# ProProject_f401_audio_adc_2024-01-29.net
KiCad netlist of a schematic drawn in EasyEDA Pro
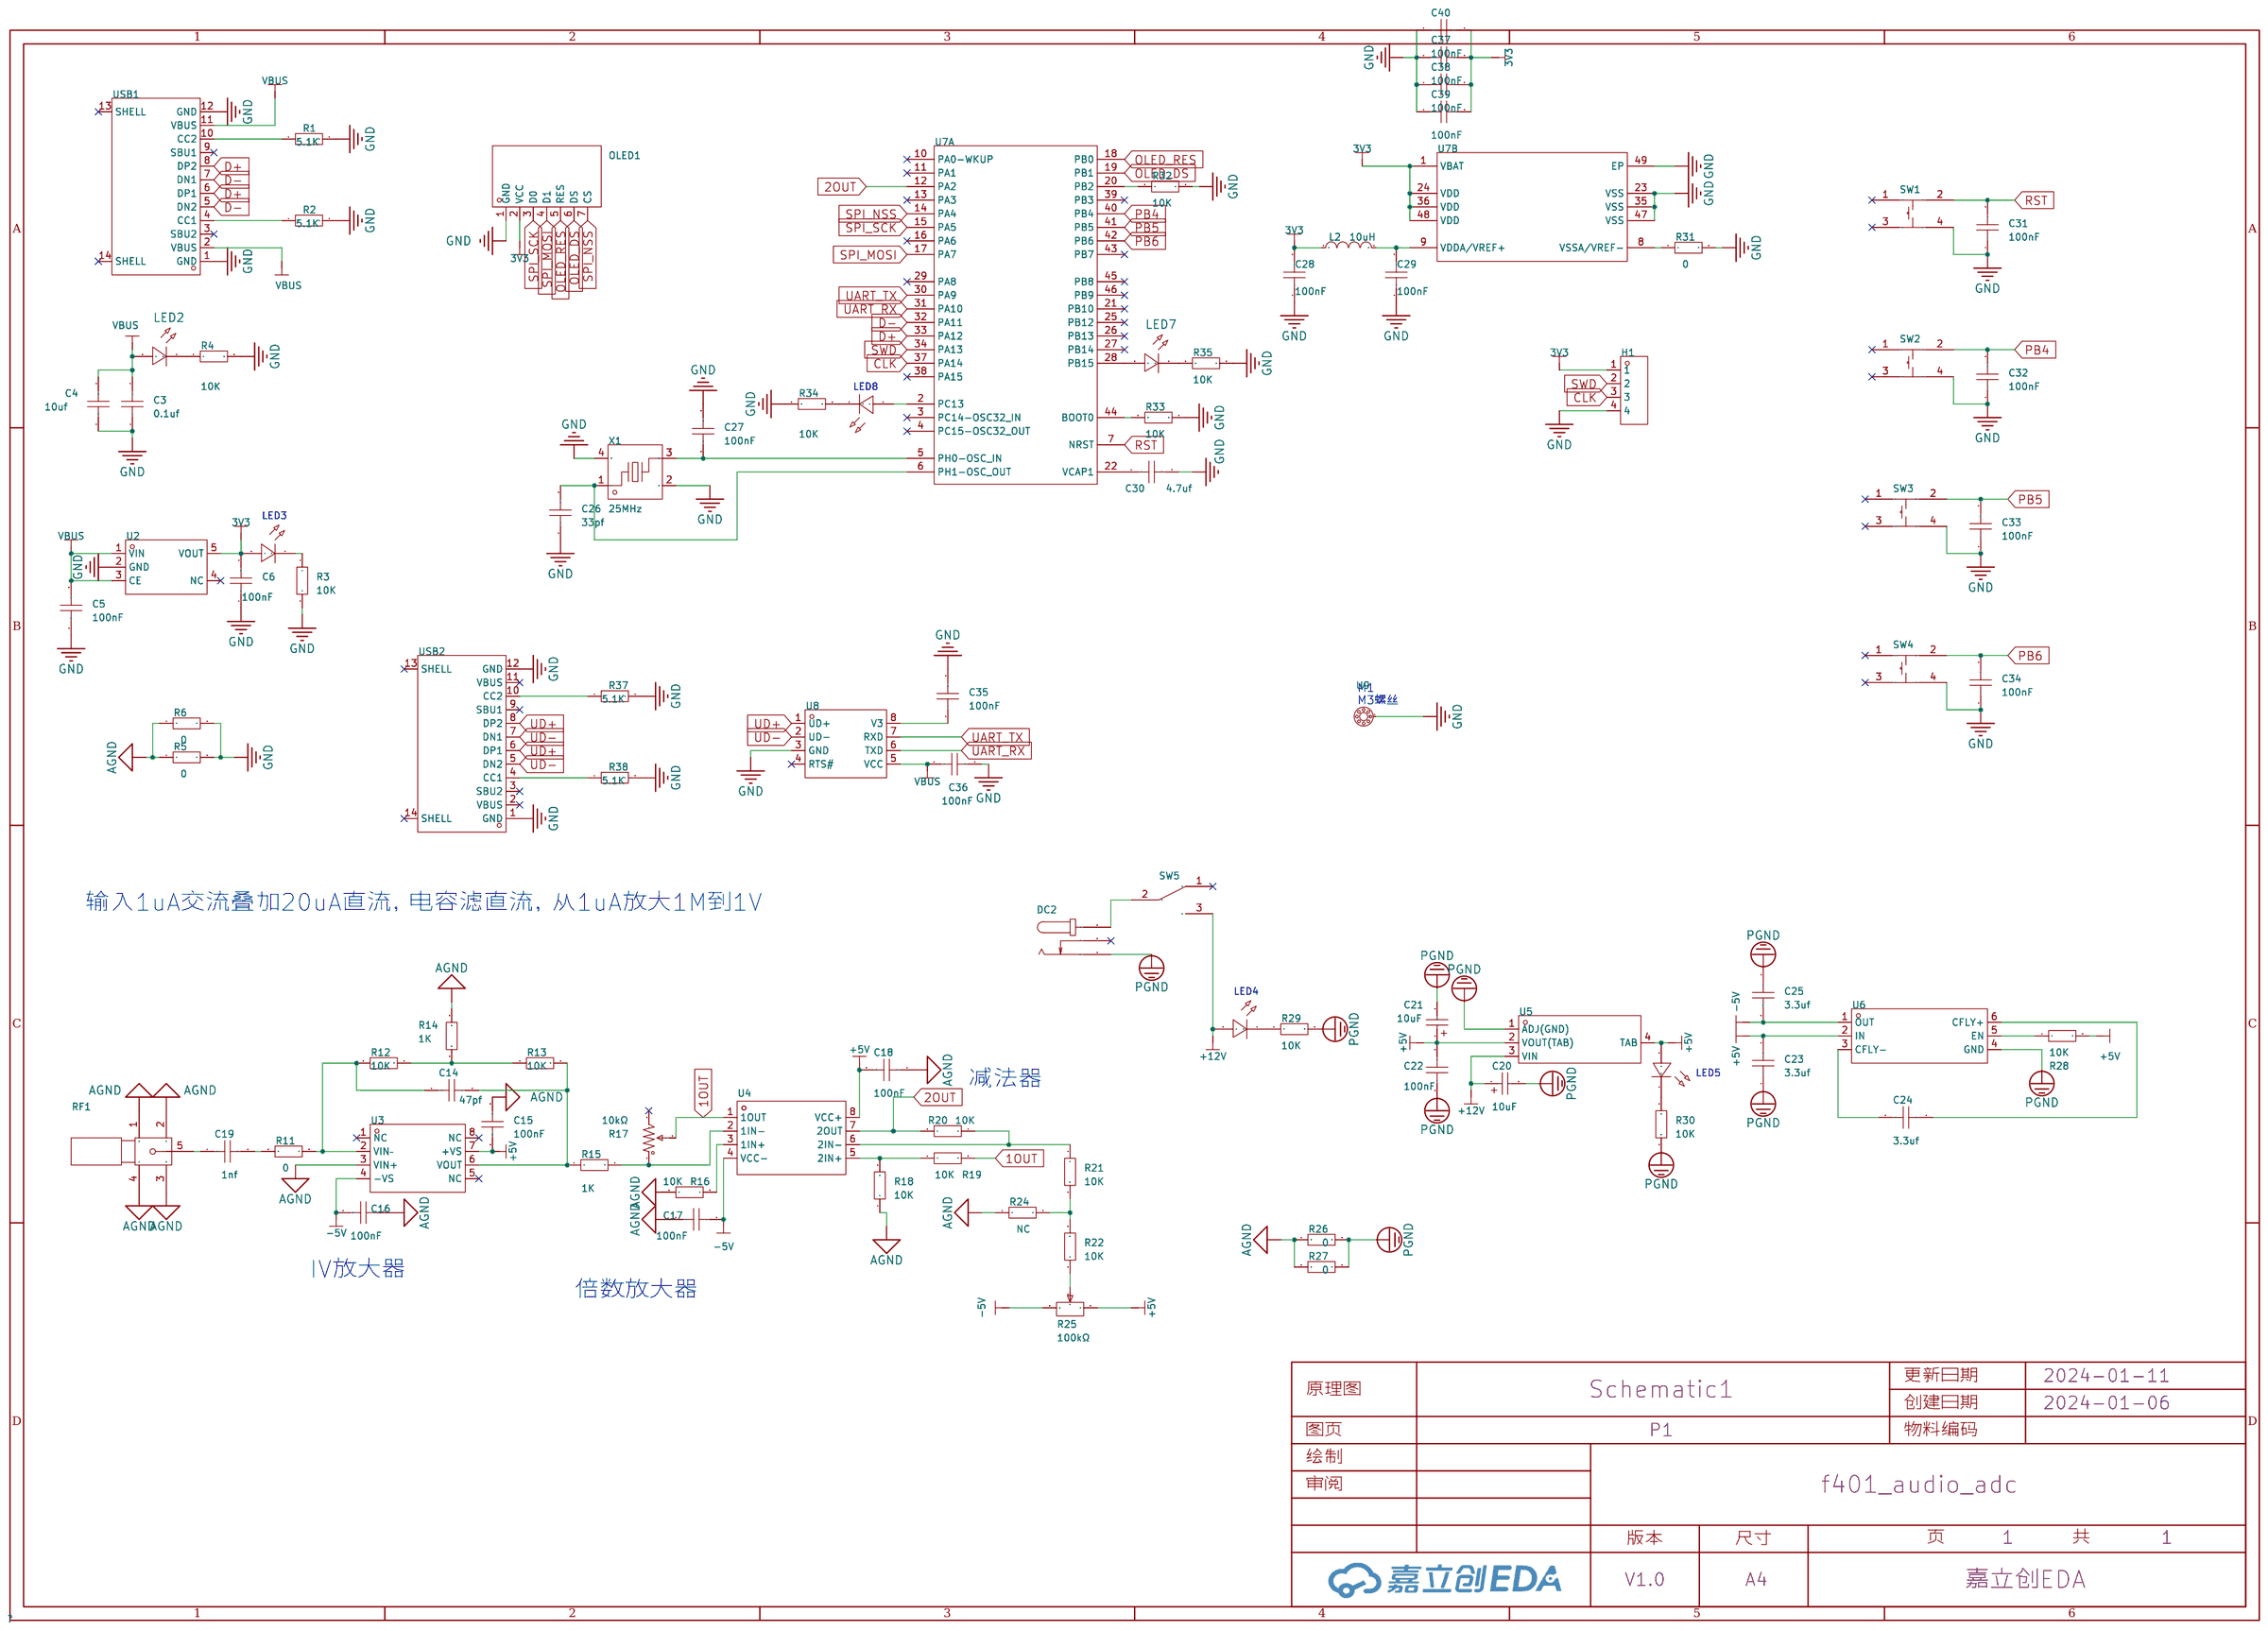
[diagram p0: schematic sheet]

(export (version "E")
  (design (tool "Eeschema 10.0.6"))
  (components
    (comp (ref "C3")
      (value "0.1uf")
      (footprint "easyedapro:C0805")
      (libsource (lib "easyedapro") (part "CapAcitance"))
    )
    (comp (ref "C4")
      (value "10uf")
      (footprint "easyedapro:C0805")
      (libsource (lib "easyedapro") (part "CapAcitance"))
    )
    (comp (ref "C5")
      (value "100nF")
      (footprint "easyedapro:C0805")
      (libsource (lib "easyedapro") (part "CapAcitance"))
    )
    (comp (ref "C6")
      (value "100nF")
      (footprint "easyedapro:C0805")
      (libsource (lib "easyedapro") (part "CapAcitance"))
    )
    (comp (ref "C14")
      (value "47pf")
      (footprint "easyedapro:C0805")
      (libsource (lib "easyedapro") (part "CapAcitance"))
    )
    (comp (ref "C15")
      (value "100nF")
      (footprint "easyedapro:C0805")
      (libsource (lib "easyedapro") (part "CapAcitance"))
    )
    (comp (ref "C16")
      (value "100nF")
      (footprint "easyedapro:C0805")
      (libsource (lib "easyedapro") (part "CapAcitance"))
    )
    (comp (ref "C17")
      (value "100nF")
      (footprint "easyedapro:C0805")
      (libsource (lib "easyedapro") (part "CapAcitance"))
    )
    (comp (ref "C18")
      (value "100nF")
      (footprint "easyedapro:C0805")
      (libsource (lib "easyedapro") (part "CapAcitance"))
    )
    (comp (ref "C19")
      (value "1nf")
      (footprint "easyedapro:C0805")
      (libsource (lib "easyedapro") (part "CapAcitance"))
    )
    (comp (ref "C20")
      (value "10uF")
      (footprint "easyedapro:CAP-SMD_L3.2-W1.6-RD-C7171")
      (description "容值:10uF;精度:±10%;额定电压:16V;等效串联电阻:3Ω@100kHz;")
      (fields (field (name "Manufacturer Part") "TAJA106K016RNJ") (field (name "Manufacturer") "Kyocera AVX"))
      (libsource (lib "easyedapro") (part "TAJA106K016RNJ"))
    )
    (comp (ref "C21")
      (value "10uF")
      (footprint "easyedapro:CAP-SMD_L3.2-W1.6-RD-C7171")
      (description "容值:10uF;精度:±10%;额定电压:16V;等效串联电阻:3Ω@100kHz;")
      (fields (field (name "Manufacturer Part") "TAJA106K016RNJ") (field (name "Manufacturer") "Kyocera AVX"))
      (libsource (lib "easyedapro") (part "TAJA106K016RNJ"))
    )
    (comp (ref "C22")
      (value "100nF")
      (footprint "easyedapro:C0805")
      (libsource (lib "easyedapro") (part "CapAcitance"))
    )
    (comp (ref "C23")
      (value "3.3uf")
      (footprint "easyedapro:C0805")
      (libsource (lib "easyedapro") (part "CapAcitance"))
    )
    (comp (ref "C24")
      (value "3.3uf")
      (footprint "easyedapro:C0805")
      (libsource (lib "easyedapro") (part "CapAcitance"))
    )
    (comp (ref "C25")
      (value "3.3uf")
      (footprint "easyedapro:C0805")
      (libsource (lib "easyedapro") (part "CapAcitance"))
    )
    (comp (ref "C26")
      (value "33pf")
      (footprint "easyedapro:C0805")
      (libsource (lib "easyedapro") (part "CapAcitance"))
    )
    (comp (ref "C27")
      (value "100nF")
      (footprint "easyedapro:C0805")
      (libsource (lib "easyedapro") (part "CapAcitance"))
    )
    (comp (ref "C28")
      (value "100nF")
      (footprint "easyedapro:C0805")
      (libsource (lib "easyedapro") (part "CapAcitance"))
    )
    (comp (ref "C29")
      (value "100nF")
      (footprint "easyedapro:C0805")
      (libsource (lib "easyedapro") (part "CapAcitance"))
    )
    (comp (ref "C30")
      (value "4.7uf")
      (footprint "easyedapro:C0805")
      (libsource (lib "easyedapro") (part "CapAcitance"))
    )
    (comp (ref "C31")
      (value "100nF")
      (footprint "easyedapro:C0805")
      (libsource (lib "easyedapro") (part "CapAcitance"))
    )
    (comp (ref "C32")
      (value "100nF")
      (footprint "easyedapro:C0805")
      (libsource (lib "easyedapro") (part "CapAcitance"))
    )
    (comp (ref "C33")
      (value "100nF")
      (footprint "easyedapro:C0805")
      (libsource (lib "easyedapro") (part "CapAcitance"))
    )
    (comp (ref "C34")
      (value "100nF")
      (footprint "easyedapro:C0805")
      (libsource (lib "easyedapro") (part "CapAcitance"))
    )
    (comp (ref "C35")
      (value "100nF")
      (footprint "easyedapro:C0805")
      (libsource (lib "easyedapro") (part "CapAcitance"))
    )
    (comp (ref "C36")
      (value "100nF")
      (footprint "easyedapro:C0805")
      (libsource (lib "easyedapro") (part "CapAcitance"))
    )
    (comp (ref "C37")
      (value "100nF")
      (footprint "easyedapro:C0805")
      (libsource (lib "easyedapro") (part "CapAcitance"))
    )
    (comp (ref "C38")
      (value "100nF")
      (footprint "easyedapro:C0805")
      (libsource (lib "easyedapro") (part "CapAcitance"))
    )
    (comp (ref "C39")
      (value "100nF")
      (footprint "easyedapro:C0805")
      (libsource (lib "easyedapro") (part "CapAcitance"))
    )
    (comp (ref "C40")
      (value "100nF")
      (footprint "easyedapro:C0805")
      (libsource (lib "easyedapro") (part "CapAcitance"))
    )
    (comp (ref "DC2")
      (value "DC005-T25")
      (footprint "easyedapro:DC-IN-TH_DC-005-20A-1")
      (description "触点内径:2.5mm;触点外径:6.3mm;额定电流:-;额定电压:-;")
      (fields (field (name "Manufacturer") "SOFNG(硕方)"))
      (libsource (lib "easyedapro") (part "DC005-2.5MM"))
    )
    (comp (ref "H1")
      (value "~")
      (footprint "easyedapro:HDR-TH_4P-P2.54-V-F")
      (libsource (lib "easyedapro") (part "2.54-1*4P母"))
    )
    (comp (ref "L2")
      (value "10uH")
      (footprint "easyedapro:L0805")
      (libsource (lib "easyedapro") (part "SDFL2012S100KTF"))
    )
    (comp (ref "LED2")
      (value "~")
      (footprint "easyedapro:LED_0805")
      (libsource (lib "easyedapro") (part "LED_R"))
    )
    (comp (ref "LED3")
      (value "~")
      (footprint "easyedapro:LED_0805")
      (libsource (lib "easyedapro") (part "LED_G"))
    )
    (comp (ref "LED4")
      (value "~")
      (footprint "easyedapro:LED_0805")
      (libsource (lib "easyedapro") (part "LED_G"))
    )
    (comp (ref "LED5")
      (value "~")
      (footprint "easyedapro:LED_0805")
      (libsource (lib "easyedapro") (part "LED_G"))
    )
    (comp (ref "LED7")
      (value "~")
      (footprint "easyedapro:LED_0805")
      (libsource (lib "easyedapro") (part "LED_R"))
    )
    (comp (ref "LED8")
      (value "~")
      (footprint "easyedapro:LED_0805")
      (libsource (lib "easyedapro") (part "LED_G"))
    )
    (comp (ref "OLED1")
      (value "HEADER7X2B")
      (footprint "easyedapro:OLED 0.96")
      (libsource (lib "easyedapro") (part "OLED 0.96"))
    )
    (comp (ref "R1") (value "5.1K") (footprint "easyedapro:R0603") (libsource (lib "easyedapro") (part "电阻")))
    (comp (ref "R2") (value "5.1K") (footprint "easyedapro:R0603") (libsource (lib "easyedapro") (part "电阻")))
    (comp (ref "R3") (value "10K") (footprint "easyedapro:R0603") (libsource (lib "easyedapro") (part "电阻")))
    (comp (ref "R4") (value "10K") (footprint "easyedapro:R0603") (libsource (lib "easyedapro") (part "电阻")))
    (comp (ref "R5") (value "0") (footprint "easyedapro:R0603") (libsource (lib "easyedapro") (part "电阻")))
    (comp (ref "R6") (value "0") (footprint "easyedapro:R0603") (libsource (lib "easyedapro") (part "电阻")))
    (comp (ref "R11") (value "0") (footprint "easyedapro:R0603") (libsource (lib "easyedapro") (part "电阻")))
    (comp (ref "R12") (value "10K") (footprint "easyedapro:R0603") (libsource (lib "easyedapro") (part "电阻")))
    (comp (ref "R13") (value "10K") (footprint "easyedapro:R0603") (libsource (lib "easyedapro") (part "电阻")))
    (comp (ref "R14") (value "1K") (footprint "easyedapro:R0603") (libsource (lib "easyedapro") (part "电阻")))
    (comp (ref "R15") (value "1K") (footprint "easyedapro:R0603") (libsource (lib "easyedapro") (part "电阻")))
    (comp (ref "R16") (value "10K") (footprint "easyedapro:R0603") (libsource (lib "easyedapro") (part "电阻")))
    (comp (ref "R17")
      (value "10kΩ")
      (footprint "easyedapro:RES-ADJ-TH_3362P")
      (description "阻值:10kΩ;精度:±10%;")
      (fields (field (name "Manufacturer Part") "3362P-1-103") (field (name "Manufacturer") "BOCHEN(博晨)"))
      (libsource (lib "easyedapro") (part "3362P-1-103_C118956"))
    )
    (comp (ref "R18") (value "10K") (footprint "easyedapro:R0603") (libsource (lib "easyedapro") (part "电阻")))
    (comp (ref "R19") (value "10K") (footprint "easyedapro:R0603") (libsource (lib "easyedapro") (part "电阻")))
    (comp (ref "R20") (value "10K") (footprint "easyedapro:R0603") (libsource (lib "easyedapro") (part "电阻")))
    (comp (ref "R21") (value "10K") (footprint "easyedapro:R0603") (libsource (lib "easyedapro") (part "电阻")))
    (comp (ref "R22") (value "10K") (footprint "easyedapro:R0603") (libsource (lib "easyedapro") (part "电阻")))
    (comp (ref "R24") (value "NC") (footprint "easyedapro:R0603") (libsource (lib "easyedapro") (part "电阻")))
    (comp (ref "R25")
      (value "100kΩ")
      (footprint "easyedapro:RES-ADJ-TH_3296W")
      (description "阻值:100kΩ;精度:±10%;")
      (fields (field (name "Manufacturer Part") "3296W-1-104LF") (field (name "Manufacturer") "BOURNS"))
      (libsource (lib "easyedapro") (part "3296W-1-104LF"))
    )
    (comp (ref "R26") (value "0") (footprint "easyedapro:R0603") (libsource (lib "easyedapro") (part "电阻")))
    (comp (ref "R27") (value "0") (footprint "easyedapro:R0603") (libsource (lib "easyedapro") (part "电阻")))
    (comp (ref "R28") (value "10K") (footprint "easyedapro:R0603") (libsource (lib "easyedapro") (part "电阻")))
    (comp (ref "R29") (value "10K") (footprint "easyedapro:R0603") (libsource (lib "easyedapro") (part "电阻")))
    (comp (ref "R30") (value "10K") (footprint "easyedapro:R0603") (libsource (lib "easyedapro") (part "电阻")))
    (comp (ref "R31") (value "0") (footprint "easyedapro:R0603") (libsource (lib "easyedapro") (part "电阻")))
    (comp (ref "R32") (value "10K") (footprint "easyedapro:R0603") (libsource (lib "easyedapro") (part "电阻")))
    (comp (ref "R33") (value "10K") (footprint "easyedapro:R0603") (libsource (lib "easyedapro") (part "电阻")))
    (comp (ref "R34") (value "10K") (footprint "easyedapro:R0603") (libsource (lib "easyedapro") (part "电阻")))
    (comp (ref "R35") (value "10K") (footprint "easyedapro:R0603") (libsource (lib "easyedapro") (part "电阻")))
    (comp (ref "R37")
      (value "5.1K")
      (footprint "easyedapro:R0603")
      (libsource (lib "easyedapro") (part "电阻"))
    )
    (comp (ref "R38")
      (value "5.1K")
      (footprint "easyedapro:R0603")
      (libsource (lib "easyedapro") (part "电阻"))
    )
    (comp (ref "RF1")
      (value "BWSMA-KWE-Z001")
      (footprint "easyedapro:SMA-TH_BWSMA-KWE-Z001")
      (fields (field (name "Manufacturer") "BAT WIRELESS(蝙蝠无线)"))
      (libsource (lib "easyedapro") (part "BWSMA-KWE-Z001"))
    )
    (comp (ref "SW1")
      (value "K2-1808SN-A3SW-01")
      (footprint "easyedapro:SW-SMD_4P-L4.2-W3.3-P2.15-LS5.1")
      (fields (field (name "Manufacturer") "韩国韩荣"))
      (libsource (lib "easyedapro") (part "K2-1808SN-A3SW-01"))
    )
    (comp (ref "SW2")
      (value "K2-1808SN-A3SW-01")
      (footprint "easyedapro:SW-SMD_4P-L4.2-W3.3-P2.15-LS5.1")
      (fields (field (name "Manufacturer") "韩国韩荣"))
      (libsource (lib "easyedapro") (part "K2-1808SN-A3SW-01"))
    )
    (comp (ref "SW3")
      (value "K2-1808SN-A3SW-01")
      (footprint "easyedapro:SW-SMD_4P-L4.2-W3.3-P2.15-LS5.1")
      (fields (field (name "Manufacturer") "韩国韩荣"))
      (libsource (lib "easyedapro") (part "K2-1808SN-A3SW-01"))
    )
    (comp (ref "SW4")
      (value "K2-1808SN-A3SW-01")
      (footprint "easyedapro:SW-SMD_4P-L4.2-W3.3-P2.15-LS5.1")
      (fields (field (name "Manufacturer") "韩国韩荣"))
      (libsource (lib "easyedapro") (part "K2-1808SN-A3SW-01"))
    )
    (comp (ref "SW5") (value "钮子开关") (libsource (lib "easyedapro") (part "钮子开关")))
    (comp (ref "U2")
      (value "RT9013-33GB-MS")
      (footprint "easyedapro:SOT-23-5_L2.9-W1.6-P0.95-LS2.8-BR")
      (description "输出类型:固定;最大输入电压:5.5V;输出电压:3.3V;输出电流:500mA;电源纹波抑制比(PSRR):75dB@(1kHz);输出极性:正极;")
      (fields (field (name "Manufacturer") "MSKSEMI(美森科)"))
      (libsource (lib "easyedapro") (part "RT9013-33GB-MS"))
    )
    (comp (ref "U3")
      (value "OPA657U")
      (footprint "easyedapro:SOIC-8_L4.9-W3.9-P1.27-LS6.0-TL")
      (description "1.6GHz、低噪声、FET 输入运算放大器 8-SOIC -40 to 85")
      (fields (field (name "Manufacturer") "TI(德州仪器)"))
      (libsource (lib "easyedapro") (part "OPA657U"))
    )
    (comp (ref "U4")
      (value "LF353DR")
      (footprint "easyedapro:SOIC-8_L5.0-W4.0-P1.27-LS6.0-BL")
      (description "运放类型:J-FET;放大器组数:2;增益带宽积（GBP）:3MHz;压摆率（SR）:13 V/us;电源电压:±3.5V ~ 18V;各通道供电电流:3.6mA;")
      (fields (field (name "Manufacturer") "TI(德州仪器)"))
      (libsource (lib "easyedapro") (part "LF353DRG4"))
    )
    (comp (ref "U5")
      (value "AMS1117-5.0")
      (footprint "easyedapro:SOT-223_L6.7-W3.5-P2.30-BR")
      (description "输出类型:固定;最大输入电压:18V;输出电压:5V;输出电流:1A;电源纹波抑制比(PSRR):60dB@(120Hz);输出极性:正;")
      (fields (field (name "Manufacturer") "UMW(友台半导体)"))
      (libsource (lib "easyedapro") (part "AMS1117-5.0_C347223"))
    )
    (comp (ref "U6")
      (value "SGM3204YN6G/TR")
      (footprint "easyedapro:SOT-23-6_L2.9-W1.6-P0.95-LS2.8-BR")
      (description "功能类型:电荷泵;输入电压:1.4V~5.5V;输出电压:-5.5V~-1.4V;输出电流(最大值):200mA;")
      (fields (field (name "Manufacturer") "SGMICRO(圣邦微)"))
      (libsource (lib "easyedapro") (part "SGM3204YN6G/TR"))
    )
    (comp (ref "U7")
      (value "STM32F401CCU6")
      (footprint "easyedapro:UFQFPN-48_L7.0-W7.0-P0.50-BL-EP")
      (fields (field (name "Manufacturer") "ST(意法半导体)"))
      (libsource (lib "easyedapro") (part "STM32F401CCU6"))
    )
    (comp (ref "U8")
      (value "CH340N")
      (footprint "easyedapro:SOP-8_L4.9-W3.9-P1.27-LS6.0-BL")
      (fields (field (name "Manufacturer") "WCH(南京沁恒)"))
      (libsource (lib "easyedapro") (part "CH340N_C2977777"))
    )
    (comp (ref "U9") (value "~") (libsource (lib "easyedapro") (part "M3焊盘")))
    (comp (ref "USB1")
      (value "TYPE-C 16PIN 2MD(073)")
      (footprint "easyedapro:USB-C-SMD_TYPE-C-6PIN-2MD-073")
      (description "连接器类型:Type-C;标准:-;公母:母;端口数量:1;触点数量:16P;安装方式:卧贴;额定电流 - 电源:5A;工作温度范围:-25°C~+85°C;")
      (fields (field (name "Manufacturer") "SHOU HAN(首韩)"))
      (libsource (lib "easyedapro") (part "TYPE-C 16PIN 2MD(073)"))
    )
    (comp (ref "USB2")
      (value "TYPE-C 16PIN 2MD(073)")
      (footprint "easyedapro:USB-C-SMD_TYPE-C-6PIN-2MD-073")
      (description "连接器类型:Type-C;标准:-;公母:母;端口数量:1;触点数量:16P;安装方式:卧贴;额定电流 - 电源:5A;工作温度范围:-25°C~+85°C;")
      (fields (field (name "Manufacturer") "SHOU HAN(首韩)"))
      (libsource (lib "easyedapro") (part "TYPE-C 16PIN 2MD(073)"))
    )
    (comp (ref "X1")
      (value "25MHz")
      (footprint "easyedapro:CRYSTAL-SMD_4P-L3.2-W2.5-BL")
      (description "频率:25MHz;负载电容:20pF;频率公差:±10ppm;")
      (fields
        (field (name "Manufacturer Part") "XL2EL89CSI-111YLC-25M")
        (field (name "Manufacturer") "YXC(扬兴晶振)")
      )
      (libsource (lib "easyedapro") (part "XL2EL89CSI-111YLC-25M"))
    )
  )
  (nets
    (net (code "1") (name "+5V") (class "Default")
      (node (ref "C15") (pin "1") (pinfunction "1_1") (pintype "input"))
      (node (ref "C18") (pin "2") (pinfunction "2_2") (pintype "input"))
      (node (ref "C21") (pin "1") (pinfunction "1_1") (pintype "input"))
      (node (ref "C22") (pin "2") (pinfunction "2_2") (pintype "input"))
      (node (ref "C23") (pin "2") (pinfunction "2_2") (pintype "input"))
      (node (ref "LED5") (pin "2") (pinfunction "A_2") (pintype "input"))
      (node (ref "R25") (pin "1") (pinfunction "1_1") (pintype "input"))
      (node (ref "R28") (pin "2") (pinfunction "2_2") (pintype "input"))
      (node (ref "U3") (pin "7") (pinfunction "+VS_7") (pintype "input"))
      (node (ref "U4") (pin "8") (pinfunction "VCC+_8") (pintype "input"))
      (node (ref "U5") (pin "2") (pinfunction "VOUT(TAB)_2") (pintype "unspecified"))
      (node (ref "U5") (pin "4") (pinfunction "TAB_4") (pintype "unspecified"))
      (node (ref "U6") (pin "2") (pinfunction "IN_2") (pintype "unspecified"))
    )
    (net (code "2") (name "+12V") (class "Default")
      (node (ref "C20") (pin "1") (pinfunction "1_1") (pintype "input"))
      (node (ref "LED4") (pin "2") (pinfunction "A_2") (pintype "input"))
      (node (ref "SW5") (pin "3") (pinfunction "3_3") (pintype "input"))
      (node (ref "U5") (pin "3") (pinfunction "VIN_3") (pintype "unspecified"))
    )
    (net (code "3") (name "-5V") (class "Default")
      (node (ref "C16") (pin "2") (pinfunction "2_2") (pintype "input"))
      (node (ref "C17") (pin "2") (pinfunction "2_2") (pintype "input"))
      (node (ref "C25") (pin "2") (pinfunction "2_2") (pintype "input"))
      (node (ref "R25") (pin "3") (pinfunction "3_3") (pintype "input"))
      (node (ref "U3") (pin "4") (pinfunction "-VS_4") (pintype "input"))
      (node (ref "U4") (pin "4") (pinfunction "VCC-_4") (pintype "input"))
      (node (ref "U6") (pin "1") (pinfunction "OUT_1") (pintype "unspecified"))
    )
    (net (code "4") (name "1OUT") (class "Default")
      (node (ref "R17") (pin "2") (pinfunction "2_2") (pintype "input"))
      (node (ref "R19") (pin "2") (pinfunction "2_2") (pintype "input"))
      (node (ref "U4") (pin "1") (pinfunction "1OUT_1") (pintype "input"))
    )
    (net (code "5") (name "2OUT") (class "Default")
      (node (ref "R20") (pin "2") (pinfunction "2_2") (pintype "input"))
      (node (ref "U4") (pin "7") (pinfunction "2OUT_7") (pintype "input"))
      (node (ref "U7") (pin "12") (pinfunction "PA2_12") (pintype "bidirectional"))
    )
    (net (code "6") (name "3V3") (class "Default")
      (node (ref "C28") (pin "2") (pinfunction "2_2") (pintype "input"))
      (node (ref "C37") (pin "2") (pinfunction "2_2") (pintype "input"))
      (node (ref "C38") (pin "2") (pinfunction "2_2") (pintype "input"))
      (node (ref "C39") (pin "2") (pinfunction "2_2") (pintype "input"))
      (node (ref "C40") (pin "2") (pinfunction "2_2") (pintype "input"))
      (node (ref "C6") (pin "2") (pinfunction "2_2") (pintype "input"))
      (node (ref "H1") (pin "1") (pinfunction "1_1") (pintype "unspecified"))
      (node (ref "L2") (pin "1") (pinfunction "1_1") (pintype "unspecified"))
      (node (ref "LED3") (pin "2") (pinfunction "A_2") (pintype "input"))
      (node (ref "OLED1") (pin "2") (pinfunction "VCC_2") (pintype "input"))
      (node (ref "U2") (pin "5") (pinfunction "VOUT_5") (pintype "unspecified"))
      (node (ref "U7") (pin "1") (pinfunction "VBAT_1") (pintype "unspecified"))
      (node (ref "U7") (pin "24") (pinfunction "VDD_24") (pintype "unspecified"))
      (node (ref "U7") (pin "36") (pinfunction "VDD_36") (pintype "unspecified"))
      (node (ref "U7") (pin "48") (pinfunction "VDD_48") (pintype "unspecified"))
    )
    (net (code "7") (name "AGND") (class "Default")
      (node (ref "C15") (pin "2") (pinfunction "2_2") (pintype "input"))
      (node (ref "C16") (pin "1") (pinfunction "1_1") (pintype "input"))
      (node (ref "C17") (pin "1") (pinfunction "1_1") (pintype "input"))
      (node (ref "C18") (pin "1") (pinfunction "1_1") (pintype "input"))
      (node (ref "R14") (pin "2") (pinfunction "2_2") (pintype "input"))
      (node (ref "R16") (pin "1") (pinfunction "1_1") (pintype "input"))
      (node (ref "R18") (pin "1") (pinfunction "1_1") (pintype "input"))
      (node (ref "R24") (pin "1") (pinfunction "1_1") (pintype "input"))
      (node (ref "R26") (pin "1") (pinfunction "1_1") (pintype "input"))
      (node (ref "R27") (pin "1") (pinfunction "1_1") (pintype "input"))
      (node (ref "R5") (pin "1") (pinfunction "1_1") (pintype "input"))
      (node (ref "R6") (pin "1") (pinfunction "1_1") (pintype "input"))
      (node (ref "RF1") (pin "1") (pinfunction "1_1") (pintype "unspecified"))
      (node (ref "RF1") (pin "2") (pinfunction "2_2") (pintype "unspecified"))
      (node (ref "RF1") (pin "3") (pinfunction "3_3") (pintype "unspecified"))
      (node (ref "RF1") (pin "4") (pinfunction "4_4") (pintype "unspecified"))
      (node (ref "U3") (pin "3") (pinfunction "VIN+_3") (pintype "input"))
    )
    (net (code "8") (name "CLK") (class "Default")
      (node (ref "H1") (pin "3") (pinfunction "3_3") (pintype "unspecified"))
      (node (ref "U7") (pin "37") (pinfunction "PA14_37") (pintype "bidirectional"))
    )
    (net (code "9") (name "D+") (class "Default")
      (node (ref "U7") (pin "33") (pinfunction "PA12_33") (pintype "bidirectional"))
      (node (ref "USB1") (pin "6") (pinfunction "DP1_6") (pintype "unspecified"))
      (node (ref "USB1") (pin "8") (pinfunction "DP2_8") (pintype "unspecified"))
    )
    (net (code "10") (name "D-") (class "Default")
      (node (ref "U7") (pin "32") (pinfunction "PA11_32") (pintype "bidirectional"))
      (node (ref "USB1") (pin "5") (pinfunction "DN2_5") (pintype "unspecified"))
      (node (ref "USB1") (pin "7") (pinfunction "DN1_7") (pintype "unspecified"))
    )
    (net (code "11") (name "GND") (class "Default")
      (node (ref "C26") (pin "1") (pinfunction "1_1") (pintype "input"))
      (node (ref "C27") (pin "2") (pinfunction "2_2") (pintype "input"))
      (node (ref "C28") (pin "1") (pinfunction "1_1") (pintype "input"))
      (node (ref "C29") (pin "1") (pinfunction "1_1") (pintype "input"))
      (node (ref "C3") (pin "1") (pinfunction "1_1") (pintype "input"))
      (node (ref "C30") (pin "2") (pinfunction "2_2") (pintype "input"))
      (node (ref "C31") (pin "1") (pinfunction "1_1") (pintype "input"))
      (node (ref "C32") (pin "1") (pinfunction "1_1") (pintype "input"))
      (node (ref "C33") (pin "1") (pinfunction "1_1") (pintype "input"))
      (node (ref "C34") (pin "1") (pinfunction "1_1") (pintype "input"))
      (node (ref "C35") (pin "2") (pinfunction "2_2") (pintype "input"))
      (node (ref "C36") (pin "2") (pinfunction "2_2") (pintype "input"))
      (node (ref "C37") (pin "1") (pinfunction "1_1") (pintype "input"))
      (node (ref "C38") (pin "1") (pinfunction "1_1") (pintype "input"))
      (node (ref "C39") (pin "1") (pinfunction "1_1") (pintype "input"))
      (node (ref "C4") (pin "1") (pinfunction "1_1") (pintype "input"))
      (node (ref "C40") (pin "1") (pinfunction "1_1") (pintype "input"))
      (node (ref "C5") (pin "1") (pinfunction "1_1") (pintype "input"))
      (node (ref "C6") (pin "1") (pinfunction "1_1") (pintype "input"))
      (node (ref "H1") (pin "4") (pinfunction "4_4") (pintype "unspecified"))
      (node (ref "OLED1") (pin "1") (pinfunction "GND_1") (pintype "input"))
      (node (ref "R1") (pin "2") (pinfunction "2_2") (pintype "input"))
      (node (ref "R2") (pin "2") (pinfunction "2_2") (pintype "input"))
      (node (ref "R3") (pin "2") (pinfunction "2_2") (pintype "input"))
      (node (ref "R31") (pin "2") (pinfunction "2_2") (pintype "input"))
      (node (ref "R32") (pin "2") (pinfunction "2_2") (pintype "input"))
      (node (ref "R33") (pin "2") (pinfunction "2_2") (pintype "input"))
      (node (ref "R34") (pin "1") (pinfunction "1_1") (pintype "input"))
      (node (ref "R35") (pin "1") (pinfunction "1_1") (pintype "input"))
      (node (ref "R37") (pin "2") (pinfunction "2_2") (pintype "input"))
      (node (ref "R38") (pin "2") (pinfunction "2_2") (pintype "input"))
      (node (ref "R4") (pin "2") (pinfunction "2_2") (pintype "input"))
      (node (ref "R5") (pin "2") (pinfunction "2_2") (pintype "input"))
      (node (ref "R6") (pin "2") (pinfunction "2_2") (pintype "input"))
      (node (ref "SW1") (pin "4") (pinfunction "4_4") (pintype "input"))
      (node (ref "SW2") (pin "4") (pinfunction "4_4") (pintype "input"))
      (node (ref "SW3") (pin "4") (pinfunction "4_4") (pintype "input"))
      (node (ref "SW4") (pin "4") (pinfunction "4_4") (pintype "input"))
      (node (ref "U2") (pin "2") (pinfunction "GND_2") (pintype "unspecified"))
      (node (ref "U7") (pin "23") (pinfunction "VSS_23") (pintype "unspecified"))
      (node (ref "U7") (pin "35") (pinfunction "VSS_35") (pintype "unspecified"))
      (node (ref "U7") (pin "47") (pinfunction "VSS_47") (pintype "unspecified"))
      (node (ref "U7") (pin "49") (pinfunction "EP_49") (pintype "unspecified"))
      (node (ref "U8") (pin "3") (pinfunction "GND_3") (pintype "unspecified"))
      (node (ref "U9") (pin "1") (pinfunction "1_1") (pintype "input"))
      (node (ref "USB1") (pin "1") (pinfunction "GND_1") (pintype "unspecified"))
      (node (ref "USB1") (pin "12") (pinfunction "GND_12") (pintype "unspecified"))
      (node (ref "USB2") (pin "1") (pinfunction "GND_1") (pintype "unspecified"))
      (node (ref "USB2") (pin "12") (pinfunction "GND_12") (pintype "unspecified"))
      (node (ref "X1") (pin "2") (pinfunction "GND_2") (pintype "input"))
      (node (ref "X1") (pin "4") (pinfunction "GND_4") (pintype "input"))
    )
    (net (code "12") (name "Net-(C19-Pad1)") (class "Default")
      (node (ref "C19") (pin "1") (pinfunction "1_1") (pintype "input"))
      (node (ref "RF1") (pin "5") (pinfunction "5_5") (pintype "unspecified"))
    )
    (net (code "13") (name "Net-(C19-Pad2)") (class "Default")
      (node (ref "C19") (pin "2") (pinfunction "2_2") (pintype "input"))
      (node (ref "R11") (pin "1") (pinfunction "1_1") (pintype "input"))
    )
    (net (code "14") (name "Net-(DC2-Pad1)") (class "Default")
      (node (ref "DC2") (pin "1") (pinfunction "1_1") (pintype "input"))
      (node (ref "SW5") (pin "2") (pinfunction "2_2") (pintype "input"))
    )
    (net (code "15") (name "Net-(LED2-C)") (class "Default")
      (node (ref "LED2") (pin "1") (pinfunction "C_1") (pintype "input"))
      (node (ref "R4") (pin "1") (pinfunction "1_1") (pintype "input"))
    )
    (net (code "16") (name "Net-(LED3-C)") (class "Default")
      (node (ref "LED3") (pin "1") (pinfunction "C_1") (pintype "input"))
      (node (ref "R3") (pin "1") (pinfunction "1_1") (pintype "input"))
    )
    (net (code "17") (name "Net-(LED4-C)") (class "Default")
      (node (ref "LED4") (pin "1") (pinfunction "C_1") (pintype "input"))
      (node (ref "R29") (pin "1") (pinfunction "1_1") (pintype "input"))
    )
    (net (code "18") (name "Net-(LED5-C)") (class "Default")
      (node (ref "LED5") (pin "1") (pinfunction "C_1") (pintype "input"))
      (node (ref "R30") (pin "1") (pinfunction "1_1") (pintype "input"))
    )
    (net (code "19") (name "Net-(LED7-A)") (class "Default")
      (node (ref "LED7") (pin "2") (pinfunction "A_2") (pintype "input"))
      (node (ref "U7") (pin "28") (pinfunction "PB15_28") (pintype "bidirectional"))
    )
    (net (code "20") (name "Net-(LED7-C)") (class "Default")
      (node (ref "LED7") (pin "1") (pinfunction "C_1") (pintype "input"))
      (node (ref "R35") (pin "2") (pinfunction "2_2") (pintype "input"))
    )
    (net (code "21") (name "Net-(LED8-A)") (class "Default")
      (node (ref "LED8") (pin "2") (pinfunction "A_2") (pintype "input"))
      (node (ref "U7") (pin "2") (pinfunction "PC13_2") (pintype "bidirectional"))
    )
    (net (code "22") (name "Net-(LED8-C)") (class "Default")
      (node (ref "LED8") (pin "1") (pinfunction "C_1") (pintype "input"))
      (node (ref "R34") (pin "2") (pinfunction "2_2") (pintype "input"))
    )
    (net (code "23") (name "Net-(R12-Pad2)") (class "Default")
      (node (ref "R12") (pin "2") (pinfunction "2_2") (pintype "input"))
      (node (ref "R13") (pin "1") (pinfunction "1_1") (pintype "input"))
      (node (ref "R14") (pin "1") (pinfunction "1_1") (pintype "input"))
    )
    (net (code "24") (name "Net-(R21-Pad2)") (class "Default")
      (node (ref "R21") (pin "2") (pinfunction "2_2") (pintype "input"))
      (node (ref "R22") (pin "2") (pinfunction "2_2") (pintype "input"))
      (node (ref "R24") (pin "2") (pinfunction "2_2") (pintype "input"))
    )
    (net (code "25") (name "Net-(R22-Pad1)") (class "Default")
      (node (ref "R22") (pin "1") (pinfunction "1_1") (pintype "input"))
      (node (ref "R25") (pin "2") (pinfunction "2_2") (pintype "input"))
    )
    (net (code "26") (name "Net-(U3-VIN–)") (class "Default")
      (node (ref "C14") (pin "1") (pinfunction "1_1") (pintype "input"))
      (node (ref "R11") (pin "2") (pinfunction "2_2") (pintype "input"))
      (node (ref "R12") (pin "1") (pinfunction "1_1") (pintype "input"))
      (node (ref "U3") (pin "2") (pinfunction "VIN–_2") (pintype "input"))
    )
    (net (code "27") (name "Net-(U3-VOUT)") (class "Default")
      (node (ref "C14") (pin "2") (pinfunction "2_2") (pintype "input"))
      (node (ref "R13") (pin "2") (pinfunction "2_2") (pintype "input"))
      (node (ref "R15") (pin "1") (pinfunction "1_1") (pintype "input"))
      (node (ref "U3") (pin "6") (pinfunction "VOUT_6") (pintype "input"))
    )
    (net (code "28") (name "Net-(U4-1IN+)") (class "Default")
      (node (ref "R16") (pin "2") (pinfunction "2_2") (pintype "input"))
      (node (ref "U4") (pin "3") (pinfunction "1IN+_3") (pintype "input"))
    )
    (net (code "29") (name "Net-(U4-1IN-)") (class "Default")
      (node (ref "R15") (pin "2") (pinfunction "2_2") (pintype "input"))
      (node (ref "R17") (pin "1") (pinfunction "1_1") (pintype "input"))
      (node (ref "U4") (pin "2") (pinfunction "1IN-_2") (pintype "input"))
    )
    (net (code "30") (name "Net-(U4-2IN+)") (class "Default")
      (node (ref "R18") (pin "2") (pinfunction "2_2") (pintype "input"))
      (node (ref "R19") (pin "1") (pinfunction "1_1") (pintype "input"))
      (node (ref "U4") (pin "5") (pinfunction "2IN+_5") (pintype "input"))
    )
    (net (code "31") (name "Net-(U4-2IN-)") (class "Default")
      (node (ref "R20") (pin "1") (pinfunction "1_1") (pintype "input"))
      (node (ref "R21") (pin "1") (pinfunction "1_1") (pintype "input"))
      (node (ref "U4") (pin "6") (pinfunction "2IN-_6") (pintype "input"))
    )
    (net (code "32") (name "Net-(U6-CFLY+)") (class "Default")
      (node (ref "C24") (pin "1") (pinfunction "1_1") (pintype "input"))
      (node (ref "U6") (pin "6") (pinfunction "CFLY+_6") (pintype "unspecified"))
    )
    (net (code "33") (name "Net-(U6-CFLY-)") (class "Default")
      (node (ref "C24") (pin "2") (pinfunction "2_2") (pintype "input"))
      (node (ref "U6") (pin "3") (pinfunction "CFLY-_3") (pintype "unspecified"))
    )
    (net (code "34") (name "Net-(U6-EN)") (class "Default")
      (node (ref "R28") (pin "1") (pinfunction "1_1") (pintype "input"))
      (node (ref "U6") (pin "5") (pinfunction "EN_5") (pintype "unspecified"))
    )
    (net (code "35") (name "Net-(U7A-BOOT0)") (class "Default")
      (node (ref "R33") (pin "1") (pinfunction "1_1") (pintype "input"))
      (node (ref "U7") (pin "44") (pinfunction "BOOT0_44") (pintype "unspecified"))
    )
    (net (code "36") (name "Net-(U7A-PB2)") (class "Default")
      (node (ref "R32") (pin "1") (pinfunction "1_1") (pintype "input"))
      (node (ref "U7") (pin "20") (pinfunction "PB2_20") (pintype "bidirectional"))
    )
    (net (code "37") (name "Net-(U7A-PH0-OSC_IN)") (class "Default")
      (node (ref "C27") (pin "1") (pinfunction "1_1") (pintype "input"))
      (node (ref "U7") (pin "5") (pinfunction "PH0-OSC_IN_5") (pintype "bidirectional"))
      (node (ref "X1") (pin "3") (pinfunction "3_3") (pintype "input"))
    )
    (net (code "38") (name "Net-(U7A-PH1-OSC_OUT)") (class "Default")
      (node (ref "C26") (pin "2") (pinfunction "2_2") (pintype "input"))
      (node (ref "U7") (pin "6") (pinfunction "PH1-OSC_OUT_6") (pintype "bidirectional"))
      (node (ref "X1") (pin "1") (pinfunction "1_1") (pintype "input"))
    )
    (net (code "39") (name "Net-(U7A-VCAP1)") (class "Default")
      (node (ref "C30") (pin "1") (pinfunction "1_1") (pintype "input"))
      (node (ref "U7") (pin "22") (pinfunction "VCAP1_22") (pintype "unspecified"))
    )
    (net (code "40") (name "Net-(U7B-VDDA{slash}VREF+)") (class "Default")
      (node (ref "C29") (pin "2") (pinfunction "2_2") (pintype "input"))
      (node (ref "L2") (pin "2") (pinfunction "2_2") (pintype "unspecified"))
      (node (ref "U7") (pin "9") (pinfunction "VDDA/VREF+_9") (pintype "unspecified"))
    )
    (net (code "41") (name "Net-(U7B-VSSA{slash}VREF-)") (class "Default")
      (node (ref "R31") (pin "1") (pinfunction "1_1") (pintype "input"))
      (node (ref "U7") (pin "8") (pinfunction "VSSA/VREF-_8") (pintype "unspecified"))
    )
    (net (code "42") (name "Net-(U8-V3)") (class "Default")
      (node (ref "C35") (pin "1") (pinfunction "1_1") (pintype "input"))
      (node (ref "U8") (pin "8") (pinfunction "V3_8") (pintype "unspecified"))
    )
    (net (code "43") (name "Net-(USB1-CC1)") (class "Default")
      (node (ref "R2") (pin "1") (pinfunction "1_1") (pintype "input"))
      (node (ref "USB1") (pin "4") (pinfunction "CC1_4") (pintype "unspecified"))
    )
    (net (code "44") (name "Net-(USB1-CC2)") (class "Default")
      (node (ref "R1") (pin "1") (pinfunction "1_1") (pintype "input"))
      (node (ref "USB1") (pin "10") (pinfunction "CC2_10") (pintype "unspecified"))
    )
    (net (code "45") (name "Net-(USB2-CC1)") (class "Default")
      (node (ref "R38") (pin "1") (pinfunction "1_1") (pintype "input"))
      (node (ref "USB2") (pin "4") (pinfunction "CC1_4") (pintype "unspecified"))
    )
    (net (code "46") (name "Net-(USB2-CC2)") (class "Default")
      (node (ref "R37") (pin "1") (pinfunction "1_1") (pintype "input"))
      (node (ref "USB2") (pin "10") (pinfunction "CC2_10") (pintype "unspecified"))
    )
    (net (code "47") (name "OLED_DS") (class "Default")
      (node (ref "OLED1") (pin "6") (pinfunction "DS_6") (pintype "input"))
      (node (ref "U7") (pin "19") (pinfunction "PB1_19") (pintype "bidirectional"))
    )
    (net (code "48") (name "OLED_RES") (class "Default")
      (node (ref "OLED1") (pin "5") (pinfunction "RES_5") (pintype "input"))
      (node (ref "U7") (pin "18") (pinfunction "PB0_18") (pintype "bidirectional"))
    )
    (net (code "49") (name "PB4") (class "Default")
      (node (ref "C32") (pin "2") (pinfunction "2_2") (pintype "input"))
      (node (ref "SW2") (pin "2") (pinfunction "2_2") (pintype "input"))
      (node (ref "U7") (pin "40") (pinfunction "PB4_40") (pintype "bidirectional"))
    )
    (net (code "50") (name "PB5") (class "Default")
      (node (ref "C33") (pin "2") (pinfunction "2_2") (pintype "input"))
      (node (ref "SW3") (pin "2") (pinfunction "2_2") (pintype "input"))
      (node (ref "U7") (pin "41") (pinfunction "PB5_41") (pintype "bidirectional"))
    )
    (net (code "51") (name "PB6") (class "Default")
      (node (ref "C34") (pin "2") (pinfunction "2_2") (pintype "input"))
      (node (ref "SW4") (pin "2") (pinfunction "2_2") (pintype "input"))
      (node (ref "U7") (pin "42") (pinfunction "PB6_42") (pintype "bidirectional"))
    )
    (net (code "52") (name "PGND") (class "Default")
      (node (ref "C20") (pin "2") (pinfunction "2_2") (pintype "input"))
      (node (ref "C21") (pin "2") (pinfunction "2_2") (pintype "input"))
      (node (ref "C22") (pin "1") (pinfunction "1_1") (pintype "input"))
      (node (ref "C23") (pin "1") (pinfunction "1_1") (pintype "input"))
      (node (ref "C25") (pin "1") (pinfunction "1_1") (pintype "input"))
      (node (ref "DC2") (pin "2") (pinfunction "2_2") (pintype "input"))
      (node (ref "R26") (pin "2") (pinfunction "2_2") (pintype "input"))
      (node (ref "R27") (pin "2") (pinfunction "2_2") (pintype "input"))
      (node (ref "R29") (pin "2") (pinfunction "2_2") (pintype "input"))
      (node (ref "R30") (pin "2") (pinfunction "2_2") (pintype "input"))
      (node (ref "U5") (pin "1") (pinfunction "ADJ(GND)_1") (pintype "unspecified"))
      (node (ref "U6") (pin "4") (pinfunction "GND_4") (pintype "unspecified"))
    )
    (net (code "53") (name "RST") (class "Default")
      (node (ref "C31") (pin "2") (pinfunction "2_2") (pintype "input"))
      (node (ref "SW1") (pin "2") (pinfunction "2_2") (pintype "input"))
      (node (ref "U7") (pin "7") (pinfunction "NRST_7") (pintype "bidirectional"))
    )
    (net (code "54") (name "SPI_MOSI") (class "Default")
      (node (ref "OLED1") (pin "4") (pinfunction "D1_4") (pintype "input"))
      (node (ref "U7") (pin "17") (pinfunction "PA7_17") (pintype "bidirectional"))
    )
    (net (code "55") (name "SPI_NSS") (class "Default")
      (node (ref "OLED1") (pin "7") (pinfunction "CS_7") (pintype "input"))
      (node (ref "U7") (pin "14") (pinfunction "PA4_14") (pintype "bidirectional"))
    )
    (net (code "56") (name "SPI_SCK") (class "Default")
      (node (ref "OLED1") (pin "3") (pinfunction "D0_3") (pintype "input"))
      (node (ref "U7") (pin "15") (pinfunction "PA5_15") (pintype "bidirectional"))
    )
    (net (code "57") (name "SWD") (class "Default")
      (node (ref "H1") (pin "2") (pinfunction "2_2") (pintype "unspecified"))
      (node (ref "U7") (pin "34") (pinfunction "PA13_34") (pintype "bidirectional"))
    )
    (net (code "58") (name "UART_RX") (class "Default")
      (node (ref "U7") (pin "31") (pinfunction "PA10_31") (pintype "bidirectional"))
      (node (ref "U8") (pin "6") (pinfunction "TXD_6") (pintype "unspecified"))
    )
    (net (code "59") (name "UART_TX") (class "Default")
      (node (ref "U7") (pin "30") (pinfunction "PA9_30") (pintype "bidirectional"))
      (node (ref "U8") (pin "7") (pinfunction "RXD_7") (pintype "unspecified"))
    )
    (net (code "60") (name "UD+") (class "Default")
      (node (ref "U8") (pin "1") (pinfunction "UD+_1") (pintype "unspecified"))
      (node (ref "USB2") (pin "6") (pinfunction "DP1_6") (pintype "unspecified"))
      (node (ref "USB2") (pin "8") (pinfunction "DP2_8") (pintype "unspecified"))
    )
    (net (code "61") (name "UD-") (class "Default")
      (node (ref "U8") (pin "2") (pinfunction "UD-_2") (pintype "unspecified"))
      (node (ref "USB2") (pin "5") (pinfunction "DN2_5") (pintype "unspecified"))
      (node (ref "USB2") (pin "7") (pinfunction "DN1_7") (pintype "unspecified"))
    )
    (net (code "62") (name "VBUS") (class "Default")
      (node (ref "C3") (pin "2") (pinfunction "2_2") (pintype "input"))
      (node (ref "C36") (pin "1") (pinfunction "1_1") (pintype "input"))
      (node (ref "C4") (pin "2") (pinfunction "2_2") (pintype "input"))
      (node (ref "C5") (pin "2") (pinfunction "2_2") (pintype "input"))
      (node (ref "LED2") (pin "2") (pinfunction "A_2") (pintype "input"))
      (node (ref "U2") (pin "1") (pinfunction "VIN_1") (pintype "unspecified"))
      (node (ref "U2") (pin "3") (pinfunction "CE_3") (pintype "unspecified"))
      (node (ref "U8") (pin "5") (pinfunction "VCC_5") (pintype "unspecified"))
      (node (ref "USB1") (pin "11") (pinfunction "VBUS_11") (pintype "unspecified"))
      (node (ref "USB1") (pin "2") (pinfunction "VBUS_2") (pintype "unspecified"))
    )
    (net (code "63") (name "unconnected-(DC2-Pad3)") (class "Default")
      (node (ref "DC2") (pin "3") (pinfunction "3_3") (pintype "input+no_connect"))
    )
    (net (code "64") (name "unconnected-(R17-Pad3)") (class "Default")
      (node (ref "R17") (pin "3") (pinfunction "3_3") (pintype "input+no_connect"))
    )
    (net (code "65") (name "unconnected-(SW1-Pad1)") (class "Default")
      (node (ref "SW1") (pin "1") (pinfunction "1_1") (pintype "input+no_connect"))
    )
    (net (code "66") (name "unconnected-(SW1-Pad3)") (class "Default")
      (node (ref "SW1") (pin "3") (pinfunction "3_3") (pintype "input+no_connect"))
    )
    (net (code "67") (name "unconnected-(SW2-Pad1)") (class "Default")
      (node (ref "SW2") (pin "1") (pinfunction "1_1") (pintype "input+no_connect"))
    )
    (net (code "68") (name "unconnected-(SW2-Pad3)") (class "Default")
      (node (ref "SW2") (pin "3") (pinfunction "3_3") (pintype "input+no_connect"))
    )
    (net (code "69") (name "unconnected-(SW3-Pad1)") (class "Default")
      (node (ref "SW3") (pin "1") (pinfunction "1_1") (pintype "input+no_connect"))
    )
    (net (code "70") (name "unconnected-(SW3-Pad3)") (class "Default")
      (node (ref "SW3") (pin "3") (pinfunction "3_3") (pintype "input+no_connect"))
    )
    (net (code "71") (name "unconnected-(SW4-Pad1)") (class "Default")
      (node (ref "SW4") (pin "1") (pinfunction "1_1") (pintype "input+no_connect"))
    )
    (net (code "72") (name "unconnected-(SW4-Pad3)") (class "Default")
      (node (ref "SW4") (pin "3") (pinfunction "3_3") (pintype "input+no_connect"))
    )
    (net (code "73") (name "unconnected-(SW5-Pad1)") (class "Default")
      (node (ref "SW5") (pin "1") (pinfunction "1_1") (pintype "input+no_connect"))
    )
    (net (code "74") (name "unconnected-(U2-NC-Pad4)") (class "Default")
      (node (ref "U2") (pin "4") (pinfunction "NC_4") (pintype "unspecified+no_connect"))
    )
    (net (code "75") (name "unconnected-(U3-NC-Pad1)") (class "Default")
      (node (ref "U3") (pin "1") (pinfunction "NC_1") (pintype "input+no_connect"))
    )
    (net (code "76") (name "unconnected-(U3-NC-Pad5)") (class "Default")
      (node (ref "U3") (pin "5") (pinfunction "NC_5") (pintype "input+no_connect"))
    )
    (net (code "77") (name "unconnected-(U3-NC-Pad8)") (class "Default")
      (node (ref "U3") (pin "8") (pinfunction "NC_8") (pintype "input+no_connect"))
    )
    (net (code "78") (name "unconnected-(U7A-PA0-WKUP-Pad10)") (class "Default")
      (node (ref "U7") (pin "10") (pinfunction "PA0-WKUP_10") (pintype "bidirectional+no_connect"))
    )
    (net (code "79") (name "unconnected-(U7A-PA1-Pad11)") (class "Default")
      (node (ref "U7") (pin "11") (pinfunction "PA1_11") (pintype "bidirectional+no_connect"))
    )
    (net (code "80") (name "unconnected-(U7A-PA3-Pad13)") (class "Default")
      (node (ref "U7") (pin "13") (pinfunction "PA3_13") (pintype "bidirectional+no_connect"))
    )
    (net (code "81") (name "unconnected-(U7A-PA6-Pad16)") (class "Default")
      (node (ref "U7") (pin "16") (pinfunction "PA6_16") (pintype "bidirectional+no_connect"))
    )
    (net (code "82") (name "unconnected-(U7A-PA8-Pad29)") (class "Default")
      (node (ref "U7") (pin "29") (pinfunction "PA8_29") (pintype "bidirectional+no_connect"))
    )
    (net (code "83") (name "unconnected-(U7A-PA15-Pad38)") (class "Default")
      (node (ref "U7") (pin "38") (pinfunction "PA15_38") (pintype "bidirectional+no_connect"))
    )
    (net (code "84") (name "unconnected-(U7A-PB3-Pad39)") (class "Default")
      (node (ref "U7") (pin "39") (pinfunction "PB3_39") (pintype "bidirectional+no_connect"))
    )
    (net (code "85") (name "unconnected-(U7A-PB7-Pad43)") (class "Default")
      (node (ref "U7") (pin "43") (pinfunction "PB7_43") (pintype "bidirectional+no_connect"))
    )
    (net (code "86") (name "unconnected-(U7A-PB8-Pad45)") (class "Default")
      (node (ref "U7") (pin "45") (pinfunction "PB8_45") (pintype "bidirectional+no_connect"))
    )
    (net (code "87") (name "unconnected-(U7A-PB9-Pad46)") (class "Default")
      (node (ref "U7") (pin "46") (pinfunction "PB9_46") (pintype "bidirectional+no_connect"))
    )
    (net (code "88") (name "unconnected-(U7A-PB10-Pad21)") (class "Default")
      (node (ref "U7") (pin "21") (pinfunction "PB10_21") (pintype "bidirectional+no_connect"))
    )
    (net (code "89") (name "unconnected-(U7A-PB12-Pad25)") (class "Default")
      (node (ref "U7") (pin "25") (pinfunction "PB12_25") (pintype "bidirectional+no_connect"))
    )
    (net (code "90") (name "unconnected-(U7A-PB13-Pad26)") (class "Default")
      (node (ref "U7") (pin "26") (pinfunction "PB13_26") (pintype "bidirectional+no_connect"))
    )
    (net (code "91") (name "unconnected-(U7A-PB14-Pad27)") (class "Default")
      (node (ref "U7") (pin "27") (pinfunction "PB14_27") (pintype "bidirectional+no_connect"))
    )
    (net (code "92") (name "unconnected-(U7A-PC14-OSC32_IN-Pad3)") (class "Default")
      (node (ref "U7") (pin "3") (pinfunction "PC14-OSC32_IN_3") (pintype "bidirectional+no_connect"))
    )
    (net (code "93") (name "unconnected-(U7A-PC15-OSC32_OUT-Pad4)") (class "Default")
      (node (ref "U7") (pin "4") (pinfunction "PC15-OSC32_OUT_4") (pintype "bidirectional+no_connect"))
    )
    (net (code "94") (name "unconnected-(U8-RTS#-Pad4)") (class "Default")
      (node (ref "U8") (pin "4") (pinfunction "RTS#_4") (pintype "unspecified+no_connect"))
    )
    (net (code "95") (name "unconnected-(USB1-SBU1-Pad9)") (class "Default")
      (node (ref "USB1") (pin "9") (pinfunction "SBU1_9") (pintype "unspecified+no_connect"))
    )
    (net (code "96") (name "unconnected-(USB1-SBU2-Pad3)") (class "Default")
      (node (ref "USB1") (pin "3") (pinfunction "SBU2_3") (pintype "unspecified+no_connect"))
    )
    (net (code "97") (name "unconnected-(USB1-SHELL-Pad13)") (class "Default")
      (node (ref "USB1") (pin "13") (pinfunction "SHELL_13") (pintype "unspecified+no_connect"))
    )
    (net (code "98") (name "unconnected-(USB1-SHELL-Pad14)") (class "Default")
      (node (ref "USB1") (pin "14") (pinfunction "SHELL_14") (pintype "unspecified+no_connect"))
    )
    (net (code "99") (name "unconnected-(USB2-SBU1-Pad9)") (class "Default")
      (node (ref "USB2") (pin "9") (pinfunction "SBU1_9") (pintype "unspecified+no_connect"))
    )
    (net (code "100") (name "unconnected-(USB2-SBU2-Pad3)") (class "Default")
      (node (ref "USB2") (pin "3") (pinfunction "SBU2_3") (pintype "unspecified+no_connect"))
    )
    (net (code "101") (name "unconnected-(USB2-SHELL-Pad13)") (class "Default")
      (node (ref "USB2") (pin "13") (pinfunction "SHELL_13") (pintype "unspecified+no_connect"))
    )
    (net (code "102") (name "unconnected-(USB2-SHELL-Pad14)") (class "Default")
      (node (ref "USB2") (pin "14") (pinfunction "SHELL_14") (pintype "unspecified+no_connect"))
    )
    (net (code "103") (name "unconnected-(USB2-VBUS-Pad2)") (class "Default")
      (node (ref "USB2") (pin "2") (pinfunction "VBUS_2") (pintype "unspecified+no_connect"))
    )
    (net (code "104") (name "unconnected-(USB2-VBUS-Pad11)") (class "Default")
      (node (ref "USB2") (pin "11") (pinfunction "VBUS_11") (pintype "unspecified+no_connect"))
    )
  )
)
